# test-fixture-SMA.net
KiCad netlist of a schematic drawn in EAGLE
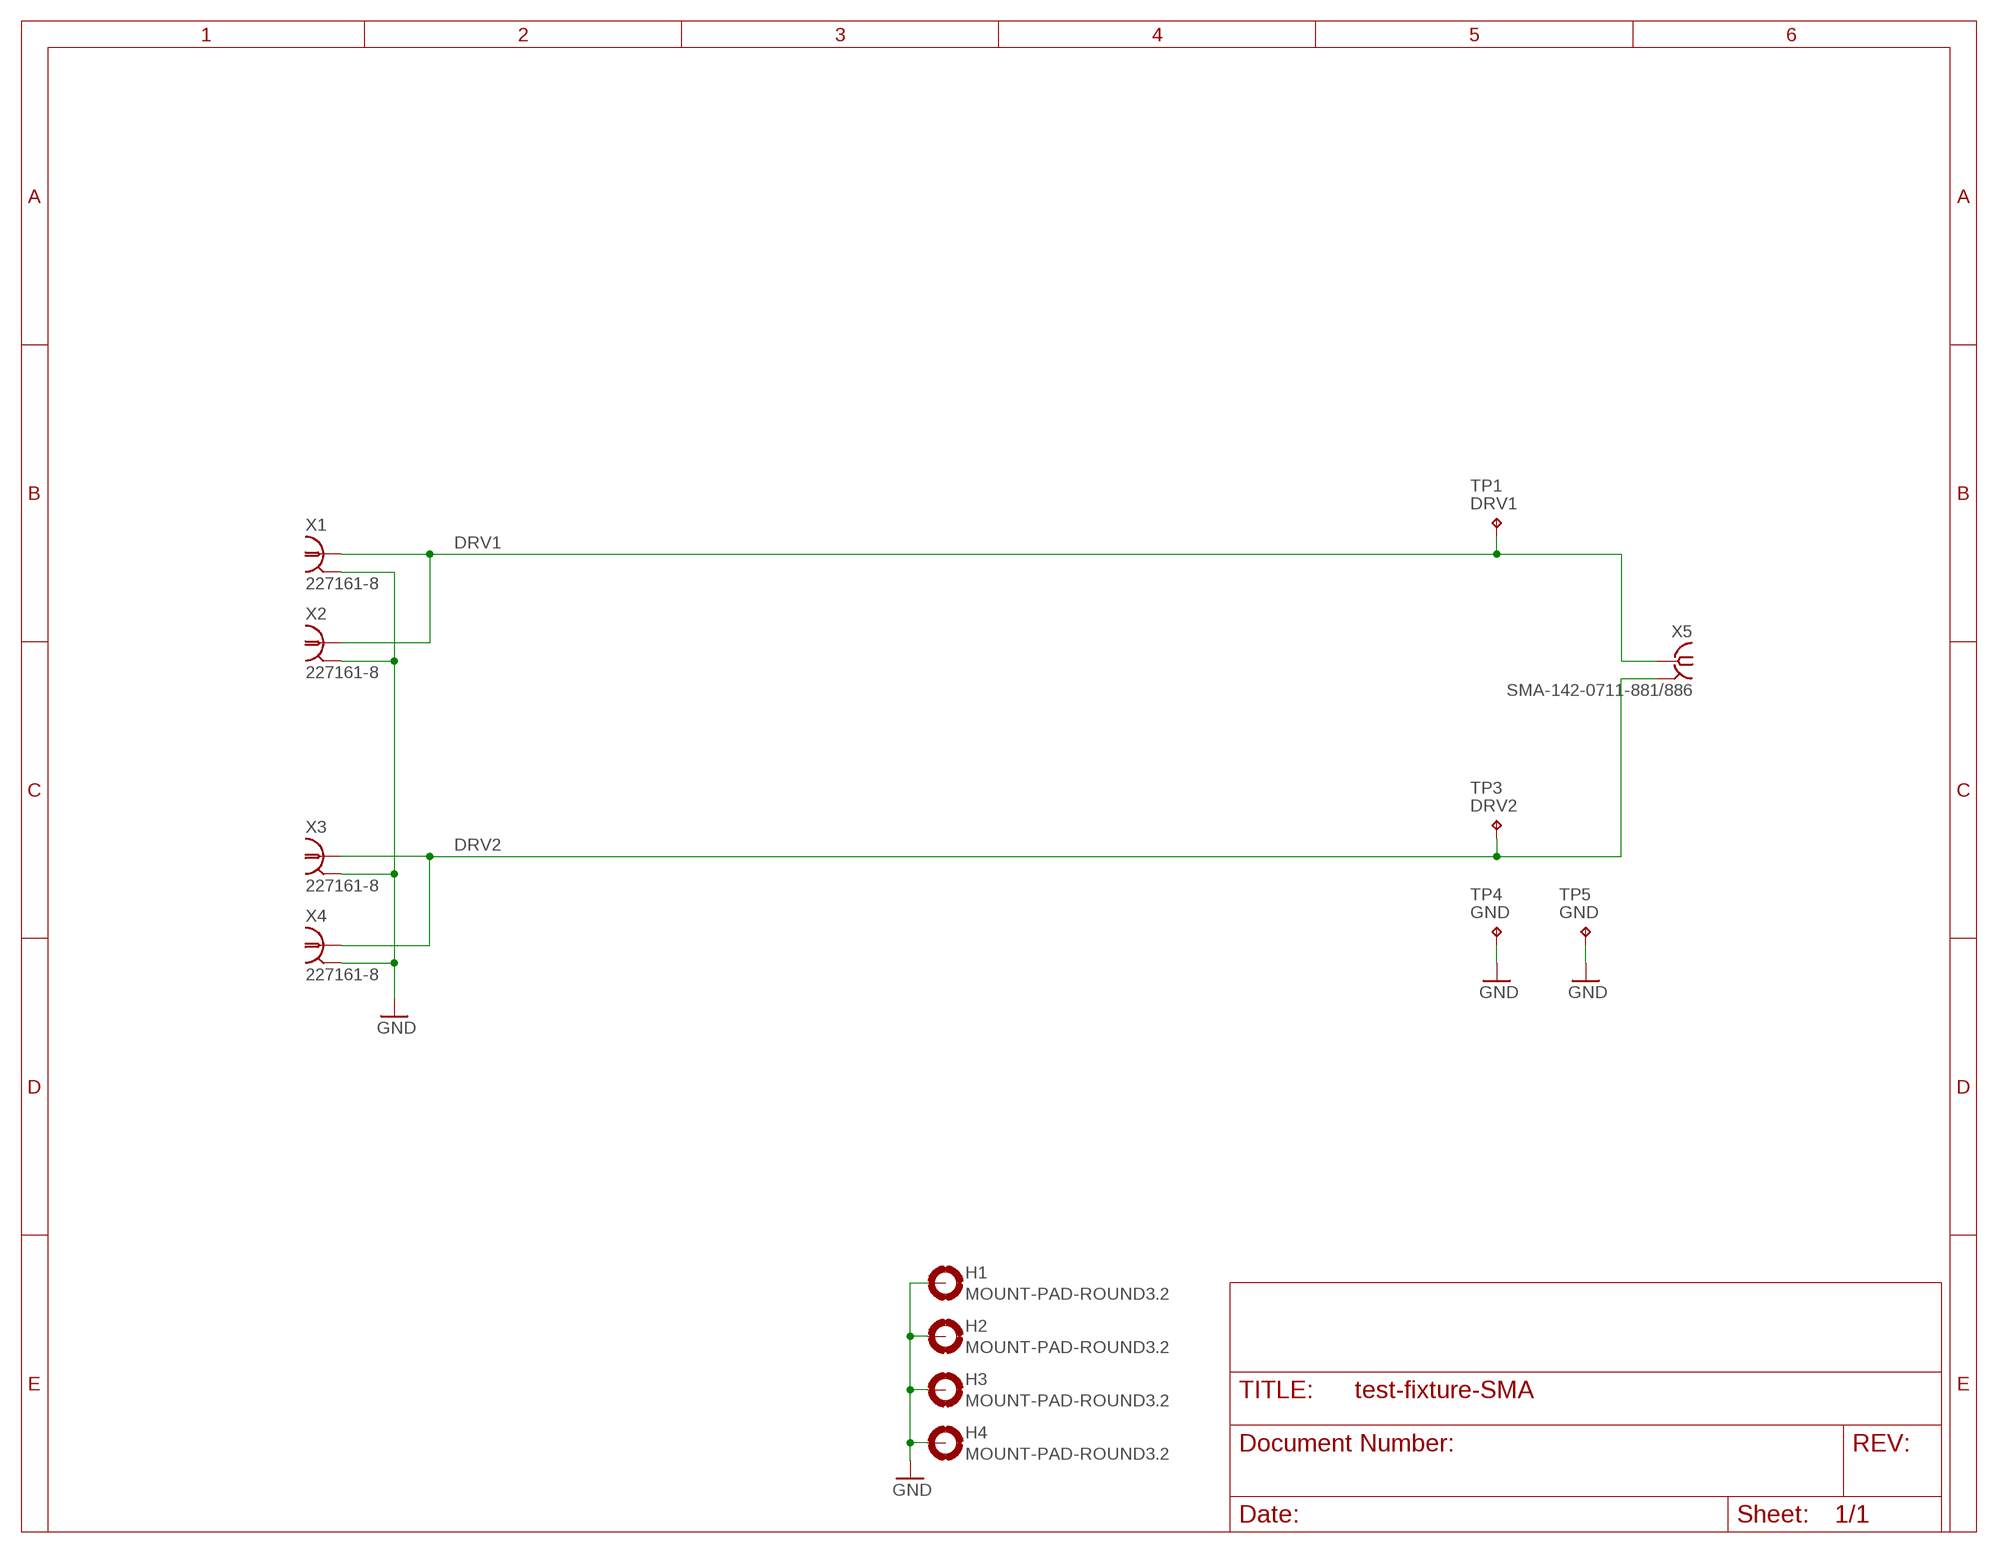
[diagram p0: schematic, sheet 1]

(export (version "E")
  (design (tool "Eeschema 10.0.6"))
  (components
    (comp (ref "H1")
      (value "MOUNT-PAD-ROUND3.2")
      (footprint "eagle-import:3,2-PAD")
      (libsource (lib "eagle-import") (part "MOUNT-PAD-ROUND3.2"))
    )
    (comp (ref "H2")
      (value "MOUNT-PAD-ROUND3.2")
      (footprint "eagle-import:3,2-PAD")
      (libsource (lib "eagle-import") (part "MOUNT-PAD-ROUND3.2"))
    )
    (comp (ref "H3")
      (value "MOUNT-PAD-ROUND3.2")
      (footprint "eagle-import:3,2-PAD")
      (libsource (lib "eagle-import") (part "MOUNT-PAD-ROUND3.2"))
    )
    (comp (ref "H4")
      (value "MOUNT-PAD-ROUND3.2")
      (footprint "eagle-import:3,2-PAD")
      (libsource (lib "eagle-import") (part "MOUNT-PAD-ROUND3.2"))
    )
    (comp (ref "TP1")
      (value "DRV1")
      (footprint "eagle-import:KEYSTONE_5000_MINIATURE")
      (libsource (lib "eagle-import") (part "KEYSTONE_5000"))
    )
    (comp (ref "TP3")
      (value "DRV2")
      (footprint "eagle-import:KEYSTONE_5000_MINIATURE")
      (libsource (lib "eagle-import") (part "KEYSTONE_5000"))
    )
    (comp (ref "TP4")
      (value "GND")
      (footprint "eagle-import:KEYSTONE_5000_MINIATURE")
      (libsource (lib "eagle-import") (part "KEYSTONE_5000"))
    )
    (comp (ref "TP5")
      (value "GND")
      (footprint "eagle-import:KEYSTONE_5000_MINIATURE")
      (libsource (lib "eagle-import") (part "KEYSTONE_5000"))
    )
    (comp (ref "X1")
      (value "227161-8")
      (footprint "eagle-import:AMP_227161")
      (libsource (lib "eagle-import") (part "?227161-8"))
    )
    (comp (ref "X2")
      (value "227161-8")
      (footprint "eagle-import:AMP_227161")
      (libsource (lib "eagle-import") (part "?227161-8"))
    )
    (comp (ref "X3")
      (value "227161-8")
      (footprint "eagle-import:AMP_227161")
      (libsource (lib "eagle-import") (part "?227161-8"))
    )
    (comp (ref "X4")
      (value "227161-8")
      (footprint "eagle-import:AMP_227161")
      (libsource (lib "eagle-import") (part "?227161-8"))
    )
    (comp (ref "X5")
      (value "SMA-142-0711-881/886")
      (footprint "eagle-import:J502-ND-142-0711-881_886")
      (fields (field (name "MF") "JOHNSON COMPONENTS") (field (name "MPN") "142-0711-881"))
      (libsource (lib "eagle-import") (part "SMA-142-0711-881/886"))
    )
  )
  (nets
    (net (code "1") (name "/DRV1") (class "Default")
      (node (ref "TP1") (pin "P$1") (pinfunction "P$1_P$1") (pintype "bidirectional"))
      (node (ref "X1") (pin "1") (pinfunction "1_1") (pintype "passive"))
      (node (ref "X2") (pin "1") (pinfunction "1_1") (pintype "passive"))
      (node (ref "X5") (pin "1") (pinfunction "1_1") (pintype "passive"))
    )
    (net (code "2") (name "/DRV2") (class "Default")
      (node (ref "TP3") (pin "P$1") (pinfunction "P$1_P$1") (pintype "bidirectional"))
      (node (ref "X3") (pin "1") (pinfunction "1_1") (pintype "passive"))
      (node (ref "X4") (pin "1") (pinfunction "1_1") (pintype "passive"))
      (node (ref "X5") (pin "G@1") (pinfunction "2_G@1") (pintype "passive"))
      (node (ref "X5") (pin "G@2") (pinfunction "2_G@2") (pintype "passive"))
      (node (ref "X5") (pin "G@3") (pinfunction "2_G@3") (pintype "passive"))
      (node (ref "X5") (pin "G@4") (pinfunction "2_G@4") (pintype "passive"))
    )
    (net (code "3") (name "GND") (class "Default")
      (node (ref "H1") (pin "B3,2") (pinfunction "MOUNT_B3,2") (pintype "passive"))
      (node (ref "H2") (pin "B3,2") (pinfunction "MOUNT_B3,2") (pintype "passive"))
      (node (ref "H3") (pin "B3,2") (pinfunction "MOUNT_B3,2") (pintype "passive"))
      (node (ref "H4") (pin "B3,2") (pinfunction "MOUNT_B3,2") (pintype "passive"))
      (node (ref "TP4") (pin "P$1") (pinfunction "P$1_P$1") (pintype "bidirectional"))
      (node (ref "TP5") (pin "P$1") (pinfunction "P$1_P$1") (pintype "bidirectional"))
      (node (ref "X1") (pin "2") (pinfunction "2_2") (pintype "passive"))
      (node (ref "X2") (pin "2") (pinfunction "2_2") (pintype "passive"))
      (node (ref "X3") (pin "2") (pinfunction "2_2") (pintype "passive"))
      (node (ref "X4") (pin "2") (pinfunction "2_2") (pintype "passive"))
    )
  )
)
